# design.net
KiCad netlist of a schematic drawn in Altium Designer
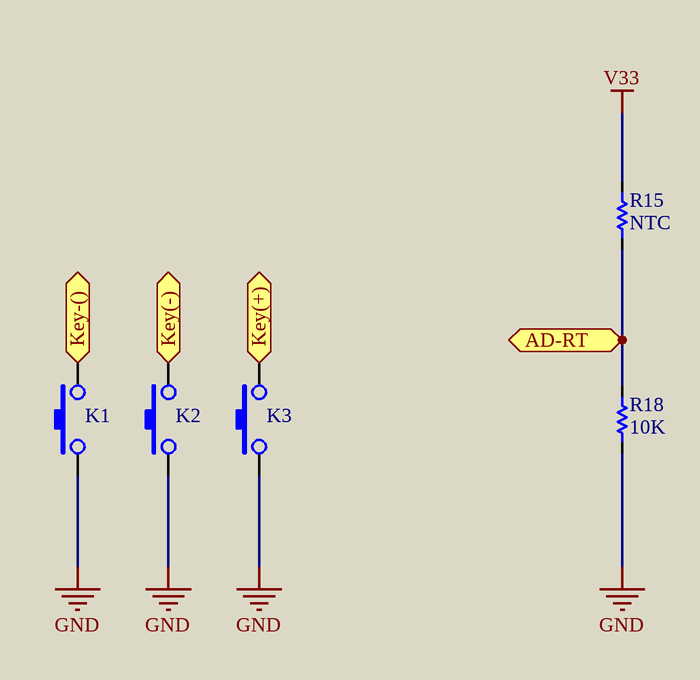
[diagram p0: 输入模块.SchDoc]

(export (version "E")
  (design (tool "Eeschema 10.0.6"))
  (components
    (comp (ref "K1") (value "SW-PB") (footprint "4KEY_SMT") (libsource (lib "素材库") (part "SW-PB")))
    (comp (ref "K2") (value "SW-PB") (footprint "4KEY_SMT") (libsource (lib "素材库") (part "SW-PB")))
    (comp (ref "K3") (value "SW-PB") (footprint "4KEY_SMT") (libsource (lib "素材库") (part "SW-PB")))
    (comp (ref "R15")
      (value "NTC")
      (footprint "6-0805_L")
      (description "Resistor")
      (fields (field (name "PUBLISHER") "Altium Limited"))
      (libsource (lib "素材库") (part "Res1_1"))
    )
    (comp (ref "R18")
      (value "10K")
      (footprint "6-0805_L")
      (description "Resistor")
      (fields (field (name "PUBLISHER") "Altium Limited"))
      (libsource (lib "素材库") (part "Res1_1"))
    )
  )
  (nets
    (net (code "1") (name "/AD-RT") (class "Default")
      (node (ref "R15") (pin "1") (pinfunction "1_1") (pintype "passive"))
      (node (ref "R18") (pin "2") (pinfunction "2_2") (pintype "passive"))
    )
    (net (code "2") (name "/Key(+)") (class "Default")
      (node (ref "K3") (pin "2") (pinfunction "2_2") (pintype "passive"))
    )
    (net (code "3") (name "/Key(-)") (class "Default")
      (node (ref "K2") (pin "2") (pinfunction "2_2") (pintype "passive"))
    )
    (net (code "4") (name "/Key-()") (class "Default")
      (node (ref "K1") (pin "2") (pinfunction "2_2") (pintype "passive"))
    )
    (net (code "5") (name "GND") (class "Default")
      (node (ref "K1") (pin "1") (pinfunction "1_1") (pintype "passive"))
      (node (ref "K2") (pin "1") (pinfunction "1_1") (pintype "passive"))
      (node (ref "K3") (pin "1") (pinfunction "1_1") (pintype "passive"))
      (node (ref "R18") (pin "1") (pinfunction "1_1") (pintype "passive"))
    )
    (net (code "6") (name "V33") (class "Default")
      (node (ref "R15") (pin "2") (pinfunction "2_2") (pintype "passive"))
    )
  )
)
